# I2C.net
KiCad netlist of a schematic drawn in Altium Designer
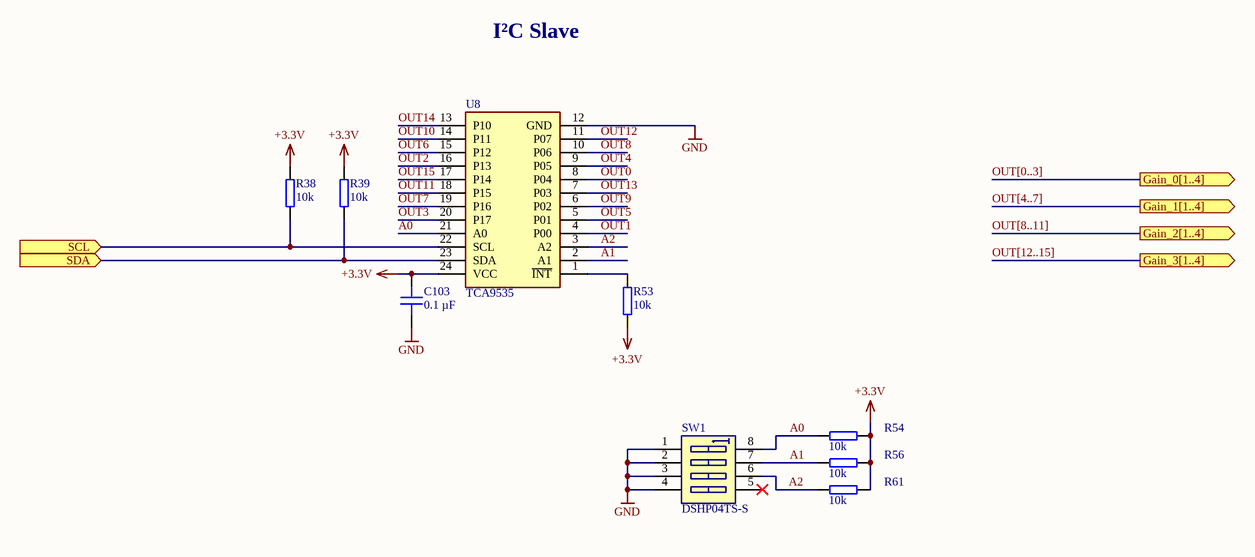
[diagram p0: I2C.SchDoc]

(export (version "E")
  (design (tool "Eeschema 10.0.6"))
  (components
    (comp (ref "C103")
      (value "0.1 µF")
      (footprint "C_0603")
      (description "Capacitor 0603, 25 VDC, 0.1 µF, X7R")
      (fields
        (field (name "MANUFACTURER PART NUMBER") "C0603C104J3REC7411")
        (field (name "MANUFACTURER") "KEMET")
        (field (name "CREATED FROM") "MGremer")
      )
      (libsource (lib "user") (part "Capacitor"))
    )
    (comp (ref "R38")
      (value "10k")
      (footprint "RES 0603_1608")
      (description "SMD resistor E24 series")
      (fields
        (field (name "MANUFACTURER PART NUMBER") "RK73B1JTTD103J")
        (field (name "MANUFACTURER") "KOA Speer")
        (field (name "CREATED FROM") "MGremer")
      )
      (libsource (lib "user") (part "Resistor"))
    )
    (comp (ref "R39")
      (value "10k")
      (footprint "RES 0603_1608")
      (description "SMD resistor E24 series")
      (fields
        (field (name "MANUFACTURER PART NUMBER") "RK73B1JTTD103J")
        (field (name "MANUFACTURER") "KOA Speer")
        (field (name "CREATED FROM") "MGremer")
      )
      (libsource (lib "user") (part "Resistor"))
    )
    (comp (ref "R53")
      (value "10k")
      (footprint "RES 0603_1608")
      (description "SMD resistor E24 series")
      (fields
        (field (name "MANUFACTURER PART NUMBER") "RK73B1JTTD103J")
        (field (name "MANUFACTURER") "KOA Speer")
        (field (name "CREATED FROM") "MGremer")
      )
      (libsource (lib "user") (part "Resistor"))
    )
    (comp (ref "R54")
      (value "10k")
      (footprint "RES 0603_1608")
      (description "SMD resistor E24 series")
      (fields
        (field (name "MANUFACTURER PART NUMBER") "RK73B1JTTD103J")
        (field (name "MANUFACTURER") "KOA Speer")
        (field (name "CREATED FROM") "MGremer")
      )
      (libsource (lib "user") (part "Resistor"))
    )
    (comp (ref "R56")
      (value "10k")
      (footprint "RES 0603_1608")
      (description "SMD resistor E24 series")
      (fields
        (field (name "MANUFACTURER PART NUMBER") "RK73B1JTTD103J")
        (field (name "MANUFACTURER") "KOA Speer")
        (field (name "CREATED FROM") "MGremer")
      )
      (libsource (lib "user") (part "Resistor"))
    )
    (comp (ref "R61")
      (value "10k")
      (footprint "RES 0603_1608")
      (description "SMD resistor E24 series")
      (fields
        (field (name "MANUFACTURER PART NUMBER") "RK73B1JTTD103J")
        (field (name "MANUFACTURER") "KOA Speer")
        (field (name "CREATED FROM") "MGremer")
      )
      (libsource (lib "user") (part "Resistor"))
    )
    (comp (ref "SW1")
      (value "DSHP04TS-S")
      (footprint "416131160804")
      (description "04p, 1.27mm Pitch, Horizontal, HP Type, SMT, flat Actuator, black, with Tape, T&R")
      (fields
        (field (name "MANUFACTURER") "XKB Connectivity")
        (field (name "LCSC PART NUMBER") "C319050")
        (field (name "CREATED FROM") "T. Wendt")
      )
      (libsource (lib "user") (part "DIP-SW-4p"))
    )
    (comp (ref "U8")
      (value "TCA9535")
      (footprint "SOP65P640X120-24N")
      (description "Low-Voltage 16-Bit I2C and SMBus Low-Power I/O Expander")
      (fields
        (field (name "MOUSER2 PART NUMBER") "595-TCA9535PWR")
        (field (name "MANUFACTURER_PART_NUMBER") "TCA9535PWR")
        (field (name "CREATED FROM") "PTurow")
      )
      (libsource (lib "user") (part "TCA9535PWR"))
    )
  )
  (nets
    (net (code "1") (name "+3.3V") (class "Default")
      (node (ref "C103") (pin "2") (pinfunction "2_2") (pintype "passive"))
      (node (ref "R38") (pin "2") (pinfunction "2_2") (pintype "passive"))
      (node (ref "R39") (pin "2") (pinfunction "2_2") (pintype "passive"))
      (node (ref "R53") (pin "1") (pinfunction "1_1") (pintype "passive"))
      (node (ref "R54") (pin "1") (pinfunction "1_1") (pintype "passive"))
      (node (ref "R56") (pin "1") (pinfunction "1_1") (pintype "passive"))
      (node (ref "R61") (pin "1") (pinfunction "1_1") (pintype "passive"))
      (node (ref "U8") (pin "24") (pinfunction "VCC_24") (pintype "passive"))
    )
    (net (code "2") (name "/A0") (class "Default")
      (node (ref "R54") (pin "2") (pinfunction "2_2") (pintype "passive"))
      (node (ref "SW1") (pin "8") (pinfunction "8_8") (pintype "passive"))
      (node (ref "U8") (pin "21") (pinfunction "A0_21") (pintype "passive"))
    )
    (net (code "3") (name "/A1") (class "Default")
      (node (ref "R56") (pin "2") (pinfunction "2_2") (pintype "passive"))
      (node (ref "SW1") (pin "7") (pinfunction "7_7") (pintype "passive"))
      (node (ref "U8") (pin "2") (pinfunction "A1_2") (pintype "passive"))
    )
    (net (code "4") (name "/A2") (class "Default")
      (node (ref "R61") (pin "2") (pinfunction "2_2") (pintype "passive"))
      (node (ref "SW1") (pin "6") (pinfunction "6_6") (pintype "passive"))
      (node (ref "U8") (pin "3") (pinfunction "A2_3") (pintype "passive"))
    )
    (net (code "5") (name "/OUT0") (class "Default")
      (node (ref "U8") (pin "8") (pinfunction "P04_8") (pintype "passive"))
    )
    (net (code "6") (name "/OUT1") (class "Default")
      (node (ref "U8") (pin "4") (pinfunction "P00_4") (pintype "passive"))
    )
    (net (code "7") (name "/OUT2") (class "Default")
      (node (ref "U8") (pin "16") (pinfunction "P13_16") (pintype "passive"))
    )
    (net (code "8") (name "/OUT3") (class "Default")
      (node (ref "U8") (pin "20") (pinfunction "P17_20") (pintype "passive"))
    )
    (net (code "9") (name "/OUT4") (class "Default")
      (node (ref "U8") (pin "9") (pinfunction "P05_9") (pintype "passive"))
    )
    (net (code "10") (name "/OUT5") (class "Default")
      (node (ref "U8") (pin "5") (pinfunction "P01_5") (pintype "passive"))
    )
    (net (code "11") (name "/OUT6") (class "Default")
      (node (ref "U8") (pin "15") (pinfunction "P12_15") (pintype "passive"))
    )
    (net (code "12") (name "/OUT7") (class "Default")
      (node (ref "U8") (pin "19") (pinfunction "P16_19") (pintype "passive"))
    )
    (net (code "13") (name "/OUT8") (class "Default")
      (node (ref "U8") (pin "10") (pinfunction "P06_10") (pintype "passive"))
    )
    (net (code "14") (name "/OUT9") (class "Default")
      (node (ref "U8") (pin "6") (pinfunction "P02_6") (pintype "passive"))
    )
    (net (code "15") (name "/OUT10") (class "Default")
      (node (ref "U8") (pin "14") (pinfunction "P11_14") (pintype "passive"))
    )
    (net (code "16") (name "/OUT11") (class "Default")
      (node (ref "U8") (pin "18") (pinfunction "P15_18") (pintype "passive"))
    )
    (net (code "17") (name "/OUT12") (class "Default")
      (node (ref "U8") (pin "11") (pinfunction "P07_11") (pintype "passive"))
    )
    (net (code "18") (name "/OUT13") (class "Default")
      (node (ref "U8") (pin "7") (pinfunction "P03_7") (pintype "passive"))
    )
    (net (code "19") (name "/OUT14") (class "Default")
      (node (ref "U8") (pin "13") (pinfunction "P10_13") (pintype "passive"))
    )
    (net (code "20") (name "/OUT15") (class "Default")
      (node (ref "U8") (pin "17") (pinfunction "P14_17") (pintype "passive"))
    )
    (net (code "25") (name "/SCL") (class "Default")
      (node (ref "R38") (pin "1") (pinfunction "1_1") (pintype "passive"))
      (node (ref "U8") (pin "22") (pinfunction "SCL_22") (pintype "passive"))
    )
    (net (code "26") (name "/SDA") (class "Default")
      (node (ref "R39") (pin "1") (pinfunction "1_1") (pintype "passive"))
      (node (ref "U8") (pin "23") (pinfunction "SDA_23") (pintype "passive"))
    )
    (net (code "27") (name "GND") (class "Default")
      (node (ref "C103") (pin "1") (pinfunction "1_1") (pintype "passive"))
      (node (ref "SW1") (pin "1") (pinfunction "1_1") (pintype "passive"))
      (node (ref "SW1") (pin "2") (pinfunction "2_2") (pintype "passive"))
      (node (ref "SW1") (pin "3") (pinfunction "3_3") (pintype "passive"))
      (node (ref "SW1") (pin "4") (pinfunction "4_4") (pintype "passive"))
      (node (ref "U8") (pin "12") (pinfunction "GND_12") (pintype "passive"))
    )
    (net (code "28") (name "Net-(U8-~{INT})") (class "Default")
      (node (ref "R53") (pin "2") (pinfunction "2_2") (pintype "passive"))
      (node (ref "U8") (pin "1") (pinfunction "~{INT}_1") (pintype "passive"))
    )
    (net (code "29") (name "unconnected-(SW1-Pad5)") (class "Default")
      (node (ref "SW1") (pin "5") (pinfunction "5_5") (pintype "passive+no_connect"))
    )
  )
)
